# Xplained_Interface.net
KiCad netlist of a schematic drawn in Altium Designer
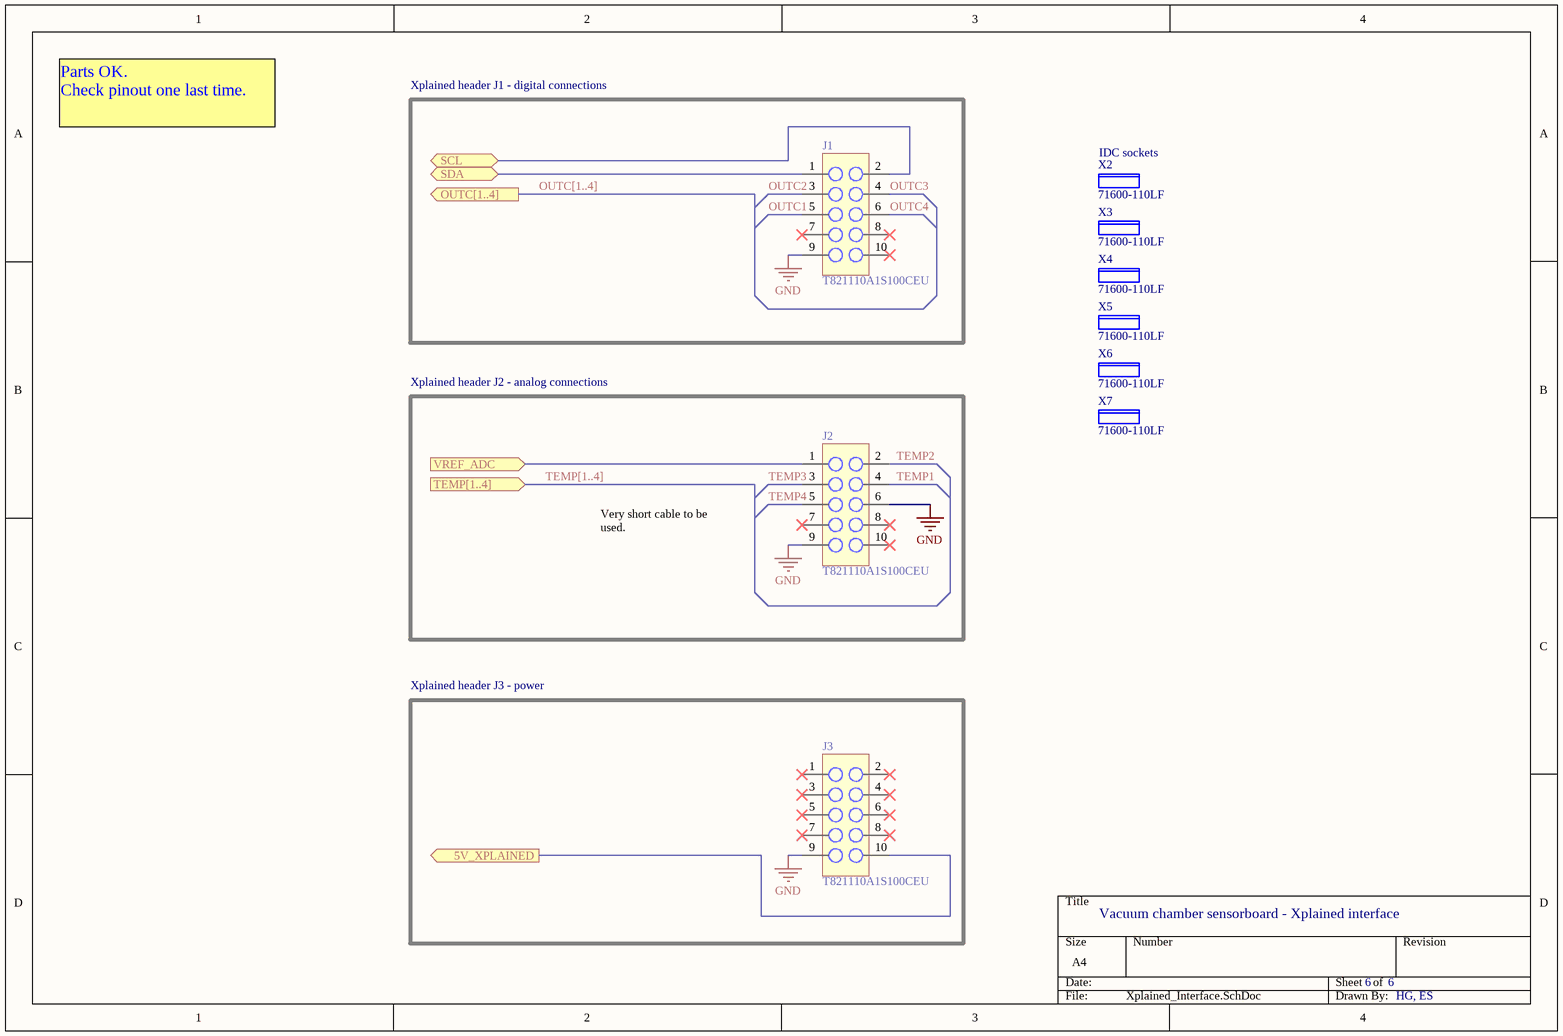
[diagram p0: Xplained_Interface.SchDoc]

(export (version "E")
  (design (tool "Eeschema 10.0.6"))
  (components
    (comp (ref "J1")
      (value "T821110A1S100CEU")
      (footprint "Header 10P")
      (description "Header, 2x5, 2.54mm")
      (fields (field (name "MANUFACTURER") "Amphenol"))
      (libsource (lib "EITlib") (part "T821110A1S100CEU"))
    )
    (comp (ref "J2")
      (value "T821110A1S100CEU")
      (footprint "Header 10P")
      (description "Header, 2x5, 2.54mm")
      (fields (field (name "MANUFACTURER") "Amphenol"))
      (libsource (lib "EITlib") (part "T821110A1S100CEU"))
    )
    (comp (ref "J3")
      (value "T821110A1S100CEU")
      (footprint "Header 10P")
      (description "Header, 2x5, 2.54mm")
      (fields (field (name "MANUFACTURER") "Amphenol"))
      (libsource (lib "EITlib") (part "T821110A1S100CEU"))
    )
    (comp (ref "X2")
      (value "71600-110LF")
      (description "IDC socket, 10way, 2.54 mm")
      (fields (field (name "MANUFACTURER") "FCI"))
      (libsource (lib "EITlib") (part "71600-110LF"))
    )
    (comp (ref "X3")
      (value "71600-110LF")
      (description "IDC socket, 10way, 2.54 mm")
      (fields (field (name "MANUFACTURER") "FCI"))
      (libsource (lib "EITlib") (part "71600-110LF"))
    )
    (comp (ref "X4")
      (value "71600-110LF")
      (description "IDC socket, 10way, 2.54 mm")
      (fields (field (name "MANUFACTURER") "FCI"))
      (libsource (lib "EITlib") (part "71600-110LF"))
    )
    (comp (ref "X5")
      (value "71600-110LF")
      (description "IDC socket, 10way, 2.54 mm")
      (fields (field (name "MANUFACTURER") "FCI"))
      (libsource (lib "EITlib") (part "71600-110LF"))
    )
    (comp (ref "X6")
      (value "71600-110LF")
      (description "IDC socket, 10way, 2.54 mm")
      (fields (field (name "MANUFACTURER") "FCI"))
      (libsource (lib "EITlib") (part "71600-110LF"))
    )
    (comp (ref "X7")
      (value "71600-110LF")
      (description "IDC socket, 10way, 2.54 mm")
      (fields (field (name "MANUFACTURER") "FCI"))
      (libsource (lib "EITlib") (part "71600-110LF"))
    )
  )
  (nets
    (net (code "1") (name "/5V_XPLAINED") (class "Default")
      (node (ref "J3") (pin "10") (pinfunction "10_10") (pintype "passive"))
    )
    (net (code "2") (name "/OUTC1") (class "Default")
      (node (ref "J1") (pin "5") (pinfunction "5_5") (pintype "passive"))
    )
    (net (code "3") (name "/OUTC2") (class "Default")
      (node (ref "J1") (pin "3") (pinfunction "3_3") (pintype "passive"))
    )
    (net (code "4") (name "/OUTC3") (class "Default")
      (node (ref "J1") (pin "4") (pinfunction "4_4") (pintype "passive"))
    )
    (net (code "5") (name "/OUTC4") (class "Default")
      (node (ref "J1") (pin "6") (pinfunction "6_6") (pintype "passive"))
    )
    (net (code "7") (name "/SCL") (class "Default")
      (node (ref "J1") (pin "2") (pinfunction "2_2") (pintype "passive"))
    )
    (net (code "8") (name "/SDA") (class "Default")
      (node (ref "J1") (pin "1") (pinfunction "1_1") (pintype "passive"))
    )
    (net (code "9") (name "/TEMP1") (class "Default")
      (node (ref "J2") (pin "4") (pinfunction "4_4") (pintype "passive"))
    )
    (net (code "10") (name "/TEMP2") (class "Default")
      (node (ref "J2") (pin "2") (pinfunction "2_2") (pintype "passive"))
    )
    (net (code "11") (name "/TEMP3") (class "Default")
      (node (ref "J2") (pin "3") (pinfunction "3_3") (pintype "passive"))
    )
    (net (code "12") (name "/TEMP4") (class "Default")
      (node (ref "J2") (pin "5") (pinfunction "5_5") (pintype "passive"))
    )
    (net (code "14") (name "/VREF_ADC") (class "Default")
      (node (ref "J2") (pin "1") (pinfunction "1_1") (pintype "passive"))
    )
    (net (code "15") (name "GND") (class "Default")
      (node (ref "J1") (pin "9") (pinfunction "9_9") (pintype "passive"))
      (node (ref "J2") (pin "6") (pinfunction "6_6") (pintype "passive"))
      (node (ref "J2") (pin "9") (pinfunction "9_9") (pintype "passive"))
      (node (ref "J3") (pin "9") (pinfunction "9_9") (pintype "passive"))
    )
    (net (code "16") (name "unconnected-(J1-Pad7)") (class "Default")
      (node (ref "J1") (pin "7") (pinfunction "7_7") (pintype "passive+no_connect"))
    )
    (net (code "17") (name "unconnected-(J1-Pad8)") (class "Default")
      (node (ref "J1") (pin "8") (pinfunction "8_8") (pintype "passive+no_connect"))
    )
    (net (code "18") (name "unconnected-(J1-Pad10)") (class "Default")
      (node (ref "J1") (pin "10") (pinfunction "10_10") (pintype "passive+no_connect"))
    )
    (net (code "19") (name "unconnected-(J2-Pad7)") (class "Default")
      (node (ref "J2") (pin "7") (pinfunction "7_7") (pintype "passive+no_connect"))
    )
    (net (code "20") (name "unconnected-(J2-Pad8)") (class "Default")
      (node (ref "J2") (pin "8") (pinfunction "8_8") (pintype "passive+no_connect"))
    )
    (net (code "21") (name "unconnected-(J2-Pad10)") (class "Default")
      (node (ref "J2") (pin "10") (pinfunction "10_10") (pintype "passive+no_connect"))
    )
    (net (code "22") (name "unconnected-(J3-Pad1)") (class "Default")
      (node (ref "J3") (pin "1") (pinfunction "1_1") (pintype "passive+no_connect"))
    )
    (net (code "23") (name "unconnected-(J3-Pad2)") (class "Default")
      (node (ref "J3") (pin "2") (pinfunction "2_2") (pintype "passive+no_connect"))
    )
    (net (code "24") (name "unconnected-(J3-Pad3)") (class "Default")
      (node (ref "J3") (pin "3") (pinfunction "3_3") (pintype "passive+no_connect"))
    )
    (net (code "25") (name "unconnected-(J3-Pad4)") (class "Default")
      (node (ref "J3") (pin "4") (pinfunction "4_4") (pintype "passive+no_connect"))
    )
    (net (code "26") (name "unconnected-(J3-Pad5)") (class "Default")
      (node (ref "J3") (pin "5") (pinfunction "5_5") (pintype "passive+no_connect"))
    )
    (net (code "27") (name "unconnected-(J3-Pad6)") (class "Default")
      (node (ref "J3") (pin "6") (pinfunction "6_6") (pintype "passive+no_connect"))
    )
    (net (code "28") (name "unconnected-(J3-Pad7)") (class "Default")
      (node (ref "J3") (pin "7") (pinfunction "7_7") (pintype "passive+no_connect"))
    )
    (net (code "29") (name "unconnected-(J3-Pad8)") (class "Default")
      (node (ref "J3") (pin "8") (pinfunction "8_8") (pintype "passive+no_connect"))
    )
  )
)
